# ESP32-MoonLolita-PCB.net
KiCad netlist of a schematic drawn in EasyEDA
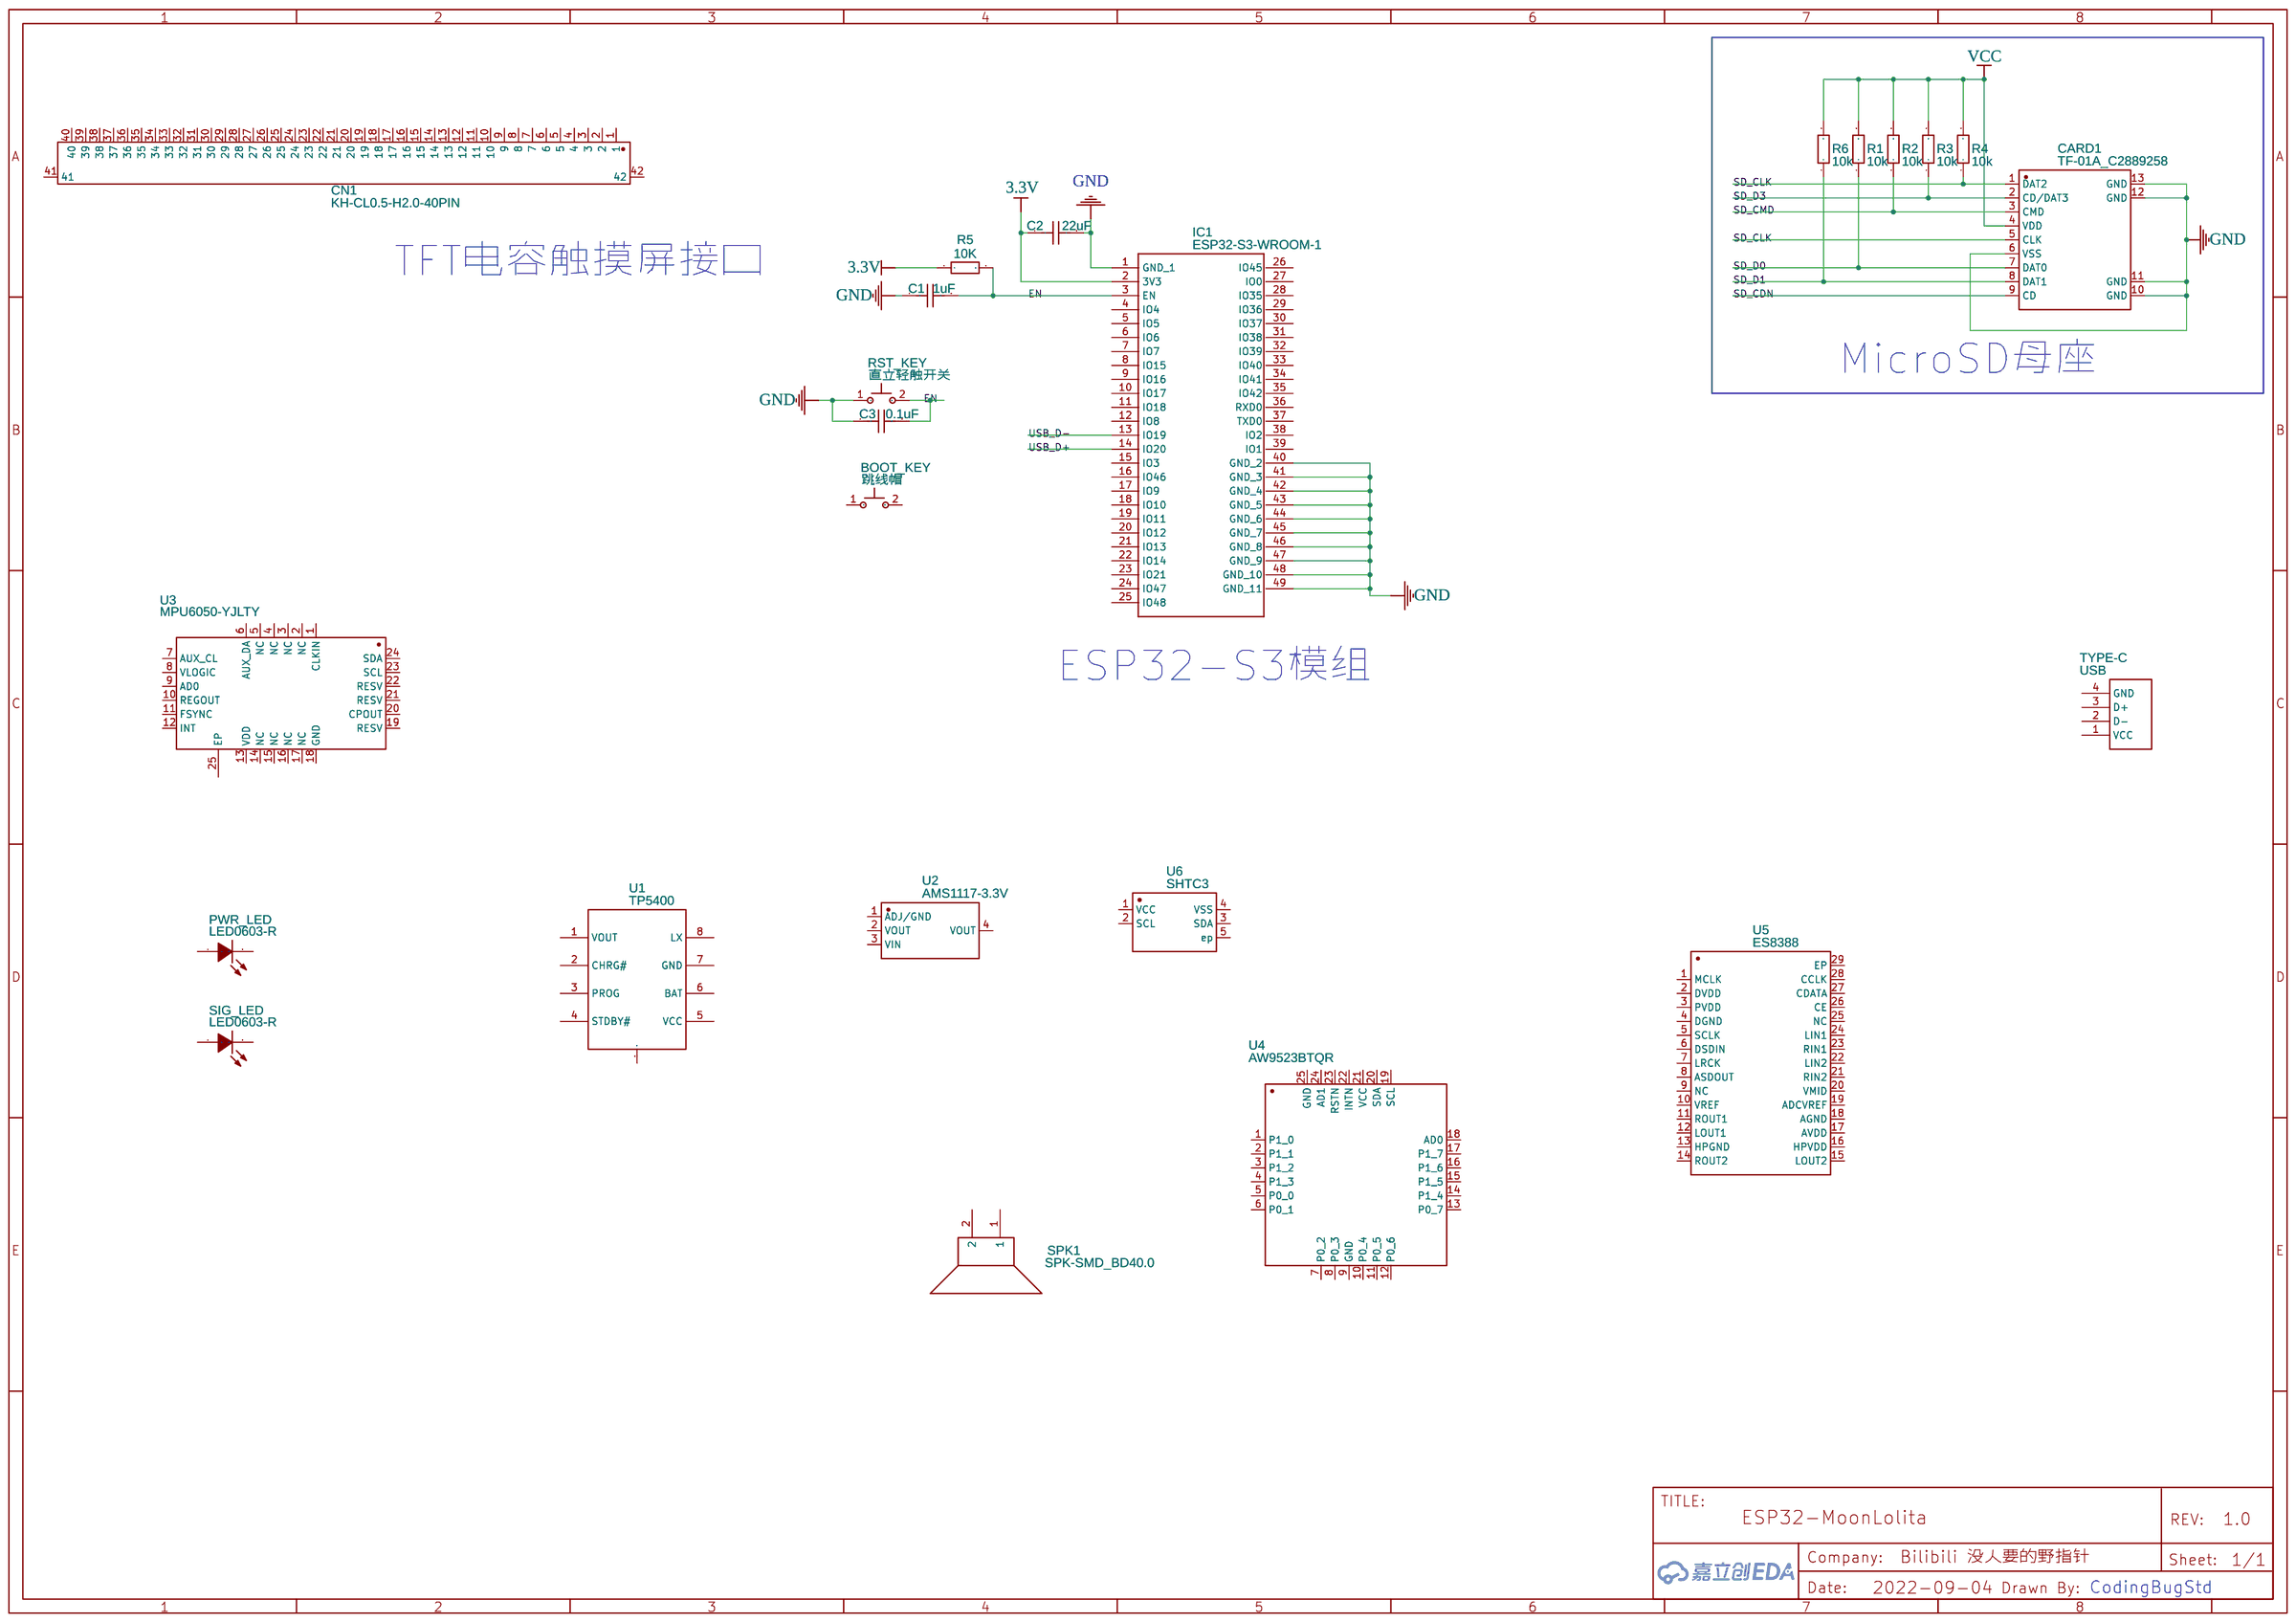
[diagram p0: schematic sheet]

(export (version "E")
  (design (tool "Eeschema 10.0.6"))
  (components
    (comp (ref "BOOT_KEY")
      (value "跳线帽")
      (fields
        (field (name "BOM_Manufacturer Part") "KSS341GLFS")
        (field (name "BOM_Supplier Part") "C221798")
      )
      (libsource (lib "") (part "KSS341GLFS_1"))
    )
    (comp (ref "C1")
      (value "1uF")
      (fields (field (name "BOM_Supplier Part") "C185991"))
      (libsource (lib "") (part "FGSM(161) 630VDC 224J 101F"))
    )
    (comp (ref "C2")
      (value "22uF")
      (fields (field (name "BOM_Supplier Part") "C185991"))
      (libsource (lib "") (part "FGSM(161) 630VDC 224J 101F"))
    )
    (comp (ref "C3")
      (value "0.1uF")
      (fields (field (name "BOM_Supplier Part") "C185991"))
      (libsource (lib "") (part "FGSM(161) 630VDC 224J 101F"))
    )
    (comp (ref "CARD1")
      (value "TF-01A_C2889258")
      (fields (field (name "BOM_Manufacturer Part") "TF-01A") (field (name "BOM_Supplier Part") "C2889258"))
      (libsource (lib "") (part "TF-01A_C2889258"))
    )
    (comp (ref "CN1")
      (value "KH-CL0.5-H2.0-40PIN")
      (fields (field (name "BOM_Supplier Part") "C2797203"))
      (libsource (lib "") (part "KH-CL0.5-H2.0-40PIN"))
    )
    (comp (ref "IC1") (value "ESP32-S3-WROOM-1") (libsource (lib "") (part "ESP32-S3-WROOM-1")))
    (comp (ref "PWR_LED")
      (value "LED0603-R")
      (fields (field (name "BOM_Supplier Part") "C9900005326"))
      (libsource (lib "") (part "LED0603-R_1"))
    )
    (comp (ref "R1")
      (value "10k")
      (fields (field (name "BOM_Manufacturer Part") "电阻0805"))
      (libsource (lib "") (part "电阻0603"))
    )
    (comp (ref "R2")
      (value "10k")
      (fields (field (name "BOM_Manufacturer Part") "电阻0805"))
      (libsource (lib "") (part "电阻0603"))
    )
    (comp (ref "R3")
      (value "10k")
      (fields (field (name "BOM_Manufacturer Part") "电阻0805"))
      (libsource (lib "") (part "电阻0603"))
    )
    (comp (ref "R4")
      (value "10k")
      (fields (field (name "BOM_Manufacturer Part") "电阻0805"))
      (libsource (lib "") (part "电阻0603"))
    )
    (comp (ref "R5")
      (value "10K")
      (fields
        (field (name "BOM_Manufacturer Part") "1206W4F1212T5E")
        (field (name "BOM_Supplier Part") "C247391")
      )
      (libsource (lib "") (part "1206W4F1212T5E"))
    )
    (comp (ref "R6")
      (value "10k")
      (fields (field (name "BOM_Manufacturer Part") "电阻0805"))
      (libsource (lib "") (part "电阻0603"))
    )
    (comp (ref "RST_KEY")
      (value "直立轻触开关")
      (fields
        (field (name "BOM_Manufacturer Part") "KSS341GLFS")
        (field (name "BOM_Supplier Part") "C221798")
      )
      (libsource (lib "") (part "KSS341GLFS"))
    )
    (comp (ref "SIG_LED")
      (value "LED0603-R")
      (fields (field (name "BOM_Supplier Part") "C9900005326"))
      (libsource (lib "") (part "LED0603-R"))
    )
    (comp (ref "SPK1") (value "SPK-SMD_BD40.0") (libsource (lib "") (part "SPK-SMD_BD40.0")))
    (comp (ref "TYPE-C")
      (value "USB")
      (fields
        (field (name "BOM_Manufacturer Part") "U-USBAR04P-F000")
        (field (name "BOM_Supplier Part") "C386740")
      )
      (libsource (lib "") (part "USB"))
    )
    (comp (ref "U1")
      (value "TP5400")
      (fields (field (name "BOM_Supplier Part") "C24154"))
      (libsource (lib "") (part "TP5400"))
    )
    (comp (ref "U2")
      (value "AMS1117-3.3V")
      (fields (field (name "BOM_Supplier Part") "C2688239"))
      (libsource (lib "") (part "AMS1117-3.3V"))
    )
    (comp (ref "U3")
      (value "MPU6050-YJLTY")
      (fields (field (name "BOM_Supplier Part") "C2912107"))
      (libsource (lib "") (part "MPU6050-YJLTY"))
    )
    (comp (ref "U4")
      (value "AW9523BTQR")
      (fields (field (name "BOM_Supplier Part") "C148077"))
      (libsource (lib "") (part "AW9523BTQR"))
    )
    (comp (ref "U5")
      (value "ES8388")
      (fields (field (name "BOM_Supplier Part") "C365736"))
      (libsource (lib "") (part "ES8388"))
    )
    (comp (ref "U6")
      (value "SHTC3")
      (fields (field (name "BOM_Supplier Part") "C194656"))
      (libsource (lib "") (part "SHTC3"))
    )
  )
  (nets
    (net (code "1") (name "/EN") (class "Default")
      (node (ref "C1") (pin "2") (pinfunction "2_2") (pintype "unspecified"))
      (node (ref "C3") (pin "2") (pinfunction "2_2") (pintype "unspecified"))
      (node (ref "IC1") (pin "3") (pinfunction "EN_3") (pintype "bidirectional"))
      (node (ref "R5") (pin "2") (pinfunction "2_2") (pintype "unspecified"))
      (node (ref "RST_KEY") (pin "2") (pinfunction "2_2") (pintype "unspecified"))
    )
    (net (code "2") (name "/SD_CDN") (class "Default")
      (node (ref "CARD1") (pin "9") (pinfunction "CD_9") (pintype "unspecified"))
    )
    (net (code "3") (name "/SD_CLK") (class "Default")
      (node (ref "CARD1") (pin "1") (pinfunction "DAT2_1") (pintype "unspecified"))
      (node (ref "CARD1") (pin "5") (pinfunction "CLK_5") (pintype "unspecified"))
      (node (ref "R4") (pin "1") (pinfunction "1_1") (pintype "input"))
    )
    (net (code "4") (name "/SD_CMD") (class "Default")
      (node (ref "CARD1") (pin "3") (pinfunction "CMD_3") (pintype "unspecified"))
      (node (ref "R2") (pin "1") (pinfunction "1_1") (pintype "input"))
    )
    (net (code "5") (name "/SD_D0") (class "Default")
      (node (ref "CARD1") (pin "7") (pinfunction "DAT0_7") (pintype "unspecified"))
      (node (ref "R1") (pin "1") (pinfunction "1_1") (pintype "input"))
    )
    (net (code "6") (name "/SD_D1") (class "Default")
      (node (ref "CARD1") (pin "8") (pinfunction "DAT1_8") (pintype "unspecified"))
      (node (ref "R6") (pin "1") (pinfunction "1_1") (pintype "input"))
    )
    (net (code "7") (name "/SD_D3") (class "Default")
      (node (ref "CARD1") (pin "2") (pinfunction "CD/DAT3_2") (pintype "unspecified"))
      (node (ref "R3") (pin "1") (pinfunction "1_1") (pintype "input"))
    )
    (net (code "8") (name "/USB_D+") (class "Default")
      (node (ref "IC1") (pin "14") (pinfunction "IO20_14") (pintype "bidirectional"))
    )
    (net (code "9") (name "/USB_D-") (class "Default")
      (node (ref "IC1") (pin "13") (pinfunction "IO19_13") (pintype "bidirectional"))
    )
    (net (code "10") (name "3.3V") (class "Default")
      (node (ref "C2") (pin "1") (pinfunction "1_1") (pintype "unspecified"))
      (node (ref "IC1") (pin "2") (pinfunction "3V3_2") (pintype "bidirectional"))
      (node (ref "R5") (pin "1") (pinfunction "1_1") (pintype "unspecified"))
    )
    (net (code "11") (name "GND") (class "Default")
      (node (ref "C1") (pin "1") (pinfunction "1_1") (pintype "unspecified"))
      (node (ref "C2") (pin "2") (pinfunction "2_2") (pintype "unspecified"))
      (node (ref "C3") (pin "1") (pinfunction "1_1") (pintype "unspecified"))
      (node (ref "CARD1") (pin "10") (pinfunction "GND_10") (pintype "unspecified"))
      (node (ref "CARD1") (pin "11") (pinfunction "GND_11") (pintype "unspecified"))
      (node (ref "CARD1") (pin "12") (pinfunction "GND_12") (pintype "unspecified"))
      (node (ref "CARD1") (pin "13") (pinfunction "GND_13") (pintype "unspecified"))
      (node (ref "CARD1") (pin "6") (pinfunction "VSS_6") (pintype "unspecified"))
      (node (ref "IC1") (pin "1") (pinfunction "GND_1_1") (pintype "bidirectional"))
      (node (ref "IC1") (pin "40") (pinfunction "GND_2_40") (pintype "bidirectional"))
      (node (ref "IC1") (pin "41") (pinfunction "GND_3_41") (pintype "bidirectional"))
      (node (ref "IC1") (pin "42") (pinfunction "GND_4_42") (pintype "bidirectional"))
      (node (ref "IC1") (pin "43") (pinfunction "GND_5_43") (pintype "bidirectional"))
      (node (ref "IC1") (pin "44") (pinfunction "GND_6_44") (pintype "bidirectional"))
      (node (ref "IC1") (pin "45") (pinfunction "GND_7_45") (pintype "bidirectional"))
      (node (ref "IC1") (pin "46") (pinfunction "GND_8_46") (pintype "bidirectional"))
      (node (ref "IC1") (pin "47") (pinfunction "GND_9_47") (pintype "bidirectional"))
      (node (ref "IC1") (pin "48") (pinfunction "GND_10_48") (pintype "bidirectional"))
      (node (ref "IC1") (pin "49") (pinfunction "GND_11_49") (pintype "bidirectional"))
      (node (ref "RST_KEY") (pin "1") (pinfunction "1_1") (pintype "unspecified"))
    )
    (net (code "12") (name "VCC") (class "Default")
      (node (ref "CARD1") (pin "4") (pinfunction "VDD_4") (pintype "unspecified"))
      (node (ref "R1") (pin "2") (pinfunction "2_2") (pintype "input"))
      (node (ref "R2") (pin "2") (pinfunction "2_2") (pintype "input"))
      (node (ref "R3") (pin "2") (pinfunction "2_2") (pintype "input"))
      (node (ref "R4") (pin "2") (pinfunction "2_2") (pintype "input"))
      (node (ref "R6") (pin "2") (pinfunction "2_2") (pintype "input"))
    )
    (net (code "13") (name "unconnected-(BOOT_KEY-Pad1)") (class "Default")
      (node (ref "BOOT_KEY") (pin "1") (pinfunction "1_1") (pintype "unspecified"))
    )
    (net (code "14") (name "unconnected-(BOOT_KEY-Pad2)") (class "Default")
      (node (ref "BOOT_KEY") (pin "2") (pinfunction "2_2") (pintype "unspecified"))
    )
    (net (code "15") (name "unconnected-(CN1-Pad1)") (class "Default")
      (node (ref "CN1") (pin "1") (pinfunction "1_1") (pintype "unspecified"))
    )
    (net (code "16") (name "unconnected-(CN1-Pad2)") (class "Default")
      (node (ref "CN1") (pin "2") (pinfunction "2_2") (pintype "unspecified"))
    )
    (net (code "17") (name "unconnected-(CN1-Pad3)") (class "Default")
      (node (ref "CN1") (pin "3") (pinfunction "3_3") (pintype "unspecified"))
    )
    (net (code "18") (name "unconnected-(CN1-Pad4)") (class "Default")
      (node (ref "CN1") (pin "4") (pinfunction "4_4") (pintype "unspecified"))
    )
    (net (code "19") (name "unconnected-(CN1-Pad5)") (class "Default")
      (node (ref "CN1") (pin "5") (pinfunction "5_5") (pintype "unspecified"))
    )
    (net (code "20") (name "unconnected-(CN1-Pad6)") (class "Default")
      (node (ref "CN1") (pin "6") (pinfunction "6_6") (pintype "unspecified"))
    )
    (net (code "21") (name "unconnected-(CN1-Pad7)") (class "Default")
      (node (ref "CN1") (pin "7") (pinfunction "7_7") (pintype "unspecified"))
    )
    (net (code "22") (name "unconnected-(CN1-Pad8)") (class "Default")
      (node (ref "CN1") (pin "8") (pinfunction "8_8") (pintype "unspecified"))
    )
    (net (code "23") (name "unconnected-(CN1-Pad9)") (class "Default")
      (node (ref "CN1") (pin "9") (pinfunction "9_9") (pintype "unspecified"))
    )
    (net (code "24") (name "unconnected-(CN1-Pad10)") (class "Default")
      (node (ref "CN1") (pin "10") (pinfunction "10_10") (pintype "unspecified"))
    )
    (net (code "25") (name "unconnected-(CN1-Pad11)") (class "Default")
      (node (ref "CN1") (pin "11") (pinfunction "11_11") (pintype "unspecified"))
    )
    (net (code "26") (name "unconnected-(CN1-Pad12)") (class "Default")
      (node (ref "CN1") (pin "12") (pinfunction "12_12") (pintype "unspecified"))
    )
    (net (code "27") (name "unconnected-(CN1-Pad13)") (class "Default")
      (node (ref "CN1") (pin "13") (pinfunction "13_13") (pintype "unspecified"))
    )
    (net (code "28") (name "unconnected-(CN1-Pad14)") (class "Default")
      (node (ref "CN1") (pin "14") (pinfunction "14_14") (pintype "unspecified"))
    )
    (net (code "29") (name "unconnected-(CN1-Pad15)") (class "Default")
      (node (ref "CN1") (pin "15") (pinfunction "15_15") (pintype "unspecified"))
    )
    (net (code "30") (name "unconnected-(CN1-Pad16)") (class "Default")
      (node (ref "CN1") (pin "16") (pinfunction "16_16") (pintype "unspecified"))
    )
    (net (code "31") (name "unconnected-(CN1-Pad17)") (class "Default")
      (node (ref "CN1") (pin "17") (pinfunction "17_17") (pintype "unspecified"))
    )
    (net (code "32") (name "unconnected-(CN1-Pad18)") (class "Default")
      (node (ref "CN1") (pin "18") (pinfunction "18_18") (pintype "unspecified"))
    )
    (net (code "33") (name "unconnected-(CN1-Pad19)") (class "Default")
      (node (ref "CN1") (pin "19") (pinfunction "19_19") (pintype "unspecified"))
    )
    (net (code "34") (name "unconnected-(CN1-Pad20)") (class "Default")
      (node (ref "CN1") (pin "20") (pinfunction "20_20") (pintype "unspecified"))
    )
    (net (code "35") (name "unconnected-(CN1-Pad21)") (class "Default")
      (node (ref "CN1") (pin "21") (pinfunction "21_21") (pintype "unspecified"))
    )
    (net (code "36") (name "unconnected-(CN1-Pad22)") (class "Default")
      (node (ref "CN1") (pin "22") (pinfunction "22_22") (pintype "unspecified"))
    )
    (net (code "37") (name "unconnected-(CN1-Pad23)") (class "Default")
      (node (ref "CN1") (pin "23") (pinfunction "23_23") (pintype "unspecified"))
    )
    (net (code "38") (name "unconnected-(CN1-Pad24)") (class "Default")
      (node (ref "CN1") (pin "24") (pinfunction "24_24") (pintype "unspecified"))
    )
    (net (code "39") (name "unconnected-(CN1-Pad25)") (class "Default")
      (node (ref "CN1") (pin "25") (pinfunction "25_25") (pintype "unspecified"))
    )
    (net (code "40") (name "unconnected-(CN1-Pad26)") (class "Default")
      (node (ref "CN1") (pin "26") (pinfunction "26_26") (pintype "unspecified"))
    )
    (net (code "41") (name "unconnected-(CN1-Pad27)") (class "Default")
      (node (ref "CN1") (pin "27") (pinfunction "27_27") (pintype "unspecified"))
    )
    (net (code "42") (name "unconnected-(CN1-Pad28)") (class "Default")
      (node (ref "CN1") (pin "28") (pinfunction "28_28") (pintype "unspecified"))
    )
    (net (code "43") (name "unconnected-(CN1-Pad29)") (class "Default")
      (node (ref "CN1") (pin "29") (pinfunction "29_29") (pintype "unspecified"))
    )
    (net (code "44") (name "unconnected-(CN1-Pad30)") (class "Default")
      (node (ref "CN1") (pin "30") (pinfunction "30_30") (pintype "unspecified"))
    )
    (net (code "45") (name "unconnected-(CN1-Pad31)") (class "Default")
      (node (ref "CN1") (pin "31") (pinfunction "31_31") (pintype "unspecified"))
    )
    (net (code "46") (name "unconnected-(CN1-Pad32)") (class "Default")
      (node (ref "CN1") (pin "32") (pinfunction "32_32") (pintype "unspecified"))
    )
    (net (code "47") (name "unconnected-(CN1-Pad33)") (class "Default")
      (node (ref "CN1") (pin "33") (pinfunction "33_33") (pintype "unspecified"))
    )
    (net (code "48") (name "unconnected-(CN1-Pad34)") (class "Default")
      (node (ref "CN1") (pin "34") (pinfunction "34_34") (pintype "unspecified"))
    )
    (net (code "49") (name "unconnected-(CN1-Pad35)") (class "Default")
      (node (ref "CN1") (pin "35") (pinfunction "35_35") (pintype "unspecified"))
    )
    (net (code "50") (name "unconnected-(CN1-Pad36)") (class "Default")
      (node (ref "CN1") (pin "36") (pinfunction "36_36") (pintype "unspecified"))
    )
    (net (code "51") (name "unconnected-(CN1-Pad37)") (class "Default")
      (node (ref "CN1") (pin "37") (pinfunction "37_37") (pintype "unspecified"))
    )
    (net (code "52") (name "unconnected-(CN1-Pad38)") (class "Default")
      (node (ref "CN1") (pin "38") (pinfunction "38_38") (pintype "unspecified"))
    )
    (net (code "53") (name "unconnected-(CN1-Pad39)") (class "Default")
      (node (ref "CN1") (pin "39") (pinfunction "39_39") (pintype "unspecified"))
    )
    (net (code "54") (name "unconnected-(CN1-Pad40)") (class "Default")
      (node (ref "CN1") (pin "40") (pinfunction "40_40") (pintype "unspecified"))
    )
    (net (code "55") (name "unconnected-(CN1-Pad41)") (class "Default")
      (node (ref "CN1") (pin "41") (pinfunction "41_41") (pintype "unspecified"))
    )
    (net (code "56") (name "unconnected-(CN1-Pad42)") (class "Default")
      (node (ref "CN1") (pin "42") (pinfunction "42_42") (pintype "unspecified"))
    )
    (net (code "57") (name "unconnected-(IC1-IO0-Pad27)") (class "Default")
      (node (ref "IC1") (pin "27") (pinfunction "IO0_27") (pintype "bidirectional"))
    )
    (net (code "58") (name "unconnected-(IC1-IO1-Pad39)") (class "Default")
      (node (ref "IC1") (pin "39") (pinfunction "IO1_39") (pintype "bidirectional"))
    )
    (net (code "59") (name "unconnected-(IC1-IO2-Pad38)") (class "Default")
      (node (ref "IC1") (pin "38") (pinfunction "IO2_38") (pintype "bidirectional"))
    )
    (net (code "60") (name "unconnected-(IC1-IO3-Pad15)") (class "Default")
      (node (ref "IC1") (pin "15") (pinfunction "IO3_15") (pintype "bidirectional"))
    )
    (net (code "61") (name "unconnected-(IC1-IO4-Pad4)") (class "Default")
      (node (ref "IC1") (pin "4") (pinfunction "IO4_4") (pintype "bidirectional"))
    )
    (net (code "62") (name "unconnected-(IC1-IO5-Pad5)") (class "Default")
      (node (ref "IC1") (pin "5") (pinfunction "IO5_5") (pintype "bidirectional"))
    )
    (net (code "63") (name "unconnected-(IC1-IO6-Pad6)") (class "Default")
      (node (ref "IC1") (pin "6") (pinfunction "IO6_6") (pintype "bidirectional"))
    )
    (net (code "64") (name "unconnected-(IC1-IO7-Pad7)") (class "Default")
      (node (ref "IC1") (pin "7") (pinfunction "IO7_7") (pintype "bidirectional"))
    )
    (net (code "65") (name "unconnected-(IC1-IO8-Pad12)") (class "Default")
      (node (ref "IC1") (pin "12") (pinfunction "IO8_12") (pintype "bidirectional"))
    )
    (net (code "66") (name "unconnected-(IC1-IO9-Pad17)") (class "Default")
      (node (ref "IC1") (pin "17") (pinfunction "IO9_17") (pintype "bidirectional"))
    )
    (net (code "67") (name "unconnected-(IC1-IO10-Pad18)") (class "Default")
      (node (ref "IC1") (pin "18") (pinfunction "IO10_18") (pintype "bidirectional"))
    )
    (net (code "68") (name "unconnected-(IC1-IO11-Pad19)") (class "Default")
      (node (ref "IC1") (pin "19") (pinfunction "IO11_19") (pintype "bidirectional"))
    )
    (net (code "69") (name "unconnected-(IC1-IO12-Pad20)") (class "Default")
      (node (ref "IC1") (pin "20") (pinfunction "IO12_20") (pintype "bidirectional"))
    )
    (net (code "70") (name "unconnected-(IC1-IO13-Pad21)") (class "Default")
      (node (ref "IC1") (pin "21") (pinfunction "IO13_21") (pintype "bidirectional"))
    )
    (net (code "71") (name "unconnected-(IC1-IO14-Pad22)") (class "Default")
      (node (ref "IC1") (pin "22") (pinfunction "IO14_22") (pintype "bidirectional"))
    )
    (net (code "72") (name "unconnected-(IC1-IO15-Pad8)") (class "Default")
      (node (ref "IC1") (pin "8") (pinfunction "IO15_8") (pintype "bidirectional"))
    )
    (net (code "73") (name "unconnected-(IC1-IO16-Pad9)") (class "Default")
      (node (ref "IC1") (pin "9") (pinfunction "IO16_9") (pintype "bidirectional"))
    )
    (net (code "74") (name "unconnected-(IC1-IO17-Pad10)") (class "Default")
      (node (ref "IC1") (pin "10") (pinfunction "IO17_10") (pintype "bidirectional"))
    )
    (net (code "75") (name "unconnected-(IC1-IO18-Pad11)") (class "Default")
      (node (ref "IC1") (pin "11") (pinfunction "IO18_11") (pintype "bidirectional"))
    )
    (net (code "76") (name "unconnected-(IC1-IO21-Pad23)") (class "Default")
      (node (ref "IC1") (pin "23") (pinfunction "IO21_23") (pintype "bidirectional"))
    )
    (net (code "77") (name "unconnected-(IC1-IO35-Pad28)") (class "Default")
      (node (ref "IC1") (pin "28") (pinfunction "IO35_28") (pintype "bidirectional"))
    )
    (net (code "78") (name "unconnected-(IC1-IO36-Pad29)") (class "Default")
      (node (ref "IC1") (pin "29") (pinfunction "IO36_29") (pintype "bidirectional"))
    )
    (net (code "79") (name "unconnected-(IC1-IO37-Pad30)") (class "Default")
      (node (ref "IC1") (pin "30") (pinfunction "IO37_30") (pintype "bidirectional"))
    )
    (net (code "80") (name "unconnected-(IC1-IO38-Pad31)") (class "Default")
      (node (ref "IC1") (pin "31") (pinfunction "IO38_31") (pintype "bidirectional"))
    )
    (net (code "81") (name "unconnected-(IC1-IO39-Pad32)") (class "Default")
      (node (ref "IC1") (pin "32") (pinfunction "IO39_32") (pintype "bidirectional"))
    )
    (net (code "82") (name "unconnected-(IC1-IO40-Pad33)") (class "Default")
      (node (ref "IC1") (pin "33") (pinfunction "IO40_33") (pintype "bidirectional"))
    )
    (net (code "83") (name "unconnected-(IC1-IO41-Pad34)") (class "Default")
      (node (ref "IC1") (pin "34") (pinfunction "IO41_34") (pintype "bidirectional"))
    )
    (net (code "84") (name "unconnected-(IC1-IO42-Pad35)") (class "Default")
      (node (ref "IC1") (pin "35") (pinfunction "IO42_35") (pintype "bidirectional"))
    )
    (net (code "85") (name "unconnected-(IC1-IO45-Pad26)") (class "Default")
      (node (ref "IC1") (pin "26") (pinfunction "IO45_26") (pintype "bidirectional"))
    )
    (net (code "86") (name "unconnected-(IC1-IO46-Pad16)") (class "Default")
      (node (ref "IC1") (pin "16") (pinfunction "IO46_16") (pintype "bidirectional"))
    )
    (net (code "87") (name "unconnected-(IC1-IO47-Pad24)") (class "Default")
      (node (ref "IC1") (pin "24") (pinfunction "IO47_24") (pintype "bidirectional"))
    )
    (net (code "88") (name "unconnected-(IC1-IO48-Pad25)") (class "Default")
      (node (ref "IC1") (pin "25") (pinfunction "IO48_25") (pintype "bidirectional"))
    )
    (net (code "89") (name "unconnected-(IC1-RXD0-Pad36)") (class "Default")
      (node (ref "IC1") (pin "36") (pinfunction "RXD0_36") (pintype "bidirectional"))
    )
    (net (code "90") (name "unconnected-(IC1-TXD0-Pad37)") (class "Default")
      (node (ref "IC1") (pin "37") (pinfunction "TXD0_37") (pintype "bidirectional"))
    )
    (net (code "91") (name "unconnected-(PWR_LED-A-Pad1)") (class "Default")
      (node (ref "PWR_LED") (pin "1") (pinfunction "A_1") (pintype "unspecified"))
    )
    (net (code "92") (name "unconnected-(PWR_LED-K-Pad2)") (class "Default")
      (node (ref "PWR_LED") (pin "2") (pinfunction "K_2") (pintype "unspecified"))
    )
    (net (code "93") (name "unconnected-(SIG_LED-A-Pad1)") (class "Default")
      (node (ref "SIG_LED") (pin "1") (pinfunction "A_1") (pintype "unspecified"))
    )
    (net (code "94") (name "unconnected-(SIG_LED-K-Pad2)") (class "Default")
      (node (ref "SIG_LED") (pin "2") (pinfunction "K_2") (pintype "unspecified"))
    )
    (net (code "95") (name "unconnected-(SPK1-Pad1)") (class "Default")
      (node (ref "SPK1") (pin "1") (pinfunction "1_1") (pintype "unspecified"))
    )
    (net (code "96") (name "unconnected-(SPK1-Pad2)") (class "Default")
      (node (ref "SPK1") (pin "2") (pinfunction "2_2") (pintype "unspecified"))
    )
    (net (code "97") (name "unconnected-(TYPE-C-D+-Pad3)") (class "Default")
      (node (ref "TYPE-C") (pin "3") (pinfunction "D+_3") (pintype "unspecified"))
    )
    (net (code "98") (name "unconnected-(TYPE-C-D--Pad2)") (class "Default")
      (node (ref "TYPE-C") (pin "2") (pinfunction "D-_2") (pintype "unspecified"))
    )
    (net (code "99") (name "unconnected-(TYPE-C-GND-Pad4)") (class "Default")
      (node (ref "TYPE-C") (pin "4") (pinfunction "GND_4") (pintype "unspecified"))
    )
    (net (code "100") (name "unconnected-(TYPE-C-VCC-Pad1)") (class "Default")
      (node (ref "TYPE-C") (pin "1") (pinfunction "VCC_1") (pintype "unspecified"))
    )
    (net (code "101") (name "unconnected-(U1-BAT-Pad6)") (class "Default")
      (node (ref "U1") (pin "6") (pinfunction "BAT_6") (pintype "unspecified"))
    )
    (net (code "102") (name "unconnected-(U1-CHRG#-Pad2)") (class "Default")
      (node (ref "U1") (pin "2") (pinfunction "CHRG#_2") (pintype "unspecified"))
    )
    (net (code "103") (name "unconnected-(U1-GND-Pad7)") (class "Default")
      (node (ref "U1") (pin "7") (pinfunction "GND_7") (pintype "unspecified"))
    )
    (net (code "104") (name "unconnected-(U1-LX-Pad8)") (class "Default")
      (node (ref "U1") (pin "8") (pinfunction "LX_8") (pintype "unspecified"))
    )
    (net (code "105") (name "unconnected-(U1-PROG-Pad3)") (class "Default")
      (node (ref "U1") (pin "3") (pinfunction "PROG_3") (pintype "unspecified"))
    )
    (net (code "106") (name "unconnected-(U1-Pad9)") (class "Default")
      (node (ref "U1") (pin "9") (pinfunction "9_9") (pintype "unspecified"))
    )
    (net (code "107") (name "unconnected-(U1-STDBY#-Pad4)") (class "Default")
      (node (ref "U1") (pin "4") (pinfunction "STDBY#_4") (pintype "unspecified"))
    )
    (net (code "108") (name "unconnected-(U1-VCC-Pad5)") (class "Default")
      (node (ref "U1") (pin "5") (pinfunction "VCC_5") (pintype "unspecified"))
    )
    (net (code "109") (name "unconnected-(U1-VOUT-Pad1)") (class "Default")
      (node (ref "U1") (pin "1") (pinfunction "VOUT_1") (pintype "unspecified"))
    )
    (net (code "110") (name "unconnected-(U2-ADJ{slash}GND-Pad1)") (class "Default")
      (node (ref "U2") (pin "1") (pinfunction "ADJ/GND_1") (pintype "unspecified"))
    )
    (net (code "111") (name "unconnected-(U2-VIN-Pad3)") (class "Default")
      (node (ref "U2") (pin "3") (pinfunction "VIN_3") (pintype "unspecified"))
    )
    (net (code "112") (name "unconnected-(U2-VOUT-Pad2)") (class "Default")
      (node (ref "U2") (pin "2") (pinfunction "VOUT_2") (pintype "unspecified"))
    )
    (net (code "113") (name "unconnected-(U2-VOUT-Pad4)") (class "Default")
      (node (ref "U2") (pin "4") (pinfunction "VOUT_4") (pintype "unspecified"))
    )
    (net (code "114") (name "unconnected-(U3-AD0-Pad9)") (class "Default")
      (node (ref "U3") (pin "9") (pinfunction "AD0_9") (pintype "unspecified"))
    )
    (net (code "115") (name "unconnected-(U3-AUX_CL-Pad7)") (class "Default")
      (node (ref "U3") (pin "7") (pinfunction "AUX_CL_7") (pintype "unspecified"))
    )
    (net (code "116") (name "unconnected-(U3-AUX_DA-Pad6)") (class "Default")
      (node (ref "U3") (pin "6") (pinfunction "AUX_DA_6") (pintype "unspecified"))
    )
    (net (code "117") (name "unconnected-(U3-CLKIN-Pad1)") (class "Default")
      (node (ref "U3") (pin "1") (pinfunction "CLKIN_1") (pintype "unspecified"))
    )
    (net (code "118") (name "unconnected-(U3-CPOUT-Pad20)") (class "Default")
      (node (ref "U3") (pin "20") (pinfunction "CPOUT_20") (pintype "unspecified"))
    )
    (net (code "119") (name "unconnected-(U3-EP-Pad25)") (class "Default")
      (node (ref "U3") (pin "25") (pinfunction "EP_25") (pintype "unspecified"))
    )
    (net (code "120") (name "unconnected-(U3-FSYNC-Pad11)") (class "Default")
      (node (ref "U3") (pin "11") (pinfunction "FSYNC_11") (pintype "unspecified"))
    )
    (net (code "121") (name "unconnected-(U3-GND-Pad18)") (class "Default")
      (node (ref "U3") (pin "18") (pinfunction "GND_18") (pintype "unspecified"))
    )
    (net (code "122") (name "unconnected-(U3-INT-Pad12)") (class "Default")
      (node (ref "U3") (pin "12") (pinfunction "INT_12") (pintype "unspecified"))
    )
    (net (code "123") (name "unconnected-(U3-NC-Pad2)") (class "Default")
      (node (ref "U3") (pin "2") (pinfunction "NC_2") (pintype "unspecified"))
    )
    (net (code "124") (name "unconnected-(U3-NC-Pad3)") (class "Default")
      (node (ref "U3") (pin "3") (pinfunction "NC_3") (pintype "unspecified"))
    )
    (net (code "125") (name "unconnected-(U3-NC-Pad4)") (class "Default")
      (node (ref "U3") (pin "4") (pinfunction "NC_4") (pintype "unspecified"))
    )
    (net (code "126") (name "unconnected-(U3-NC-Pad5)") (class "Default")
      (node (ref "U3") (pin "5") (pinfunction "NC_5") (pintype "unspecified"))
    )
    (net (code "127") (name "unconnected-(U3-NC-Pad14)") (class "Default")
      (node (ref "U3") (pin "14") (pinfunction "NC_14") (pintype "unspecified"))
    )
    (net (code "128") (name "unconnected-(U3-NC-Pad15)") (class "Default")
      (node (ref "U3") (pin "15") (pinfunction "NC_15") (pintype "unspecified"))
    )
    (net (code "129") (name "unconnected-(U3-NC-Pad16)") (class "Default")
      (node (ref "U3") (pin "16") (pinfunction "NC_16") (pintype "unspecified"))
    )
    (net (code "130") (name "unconnected-(U3-NC-Pad17)") (class "Default")
      (node (ref "U3") (pin "17") (pinfunction "NC_17") (pintype "unspecified"))
    )
    (net (code "131") (name "unconnected-(U3-REGOUT-Pad10)") (class "Default")
      (node (ref "U3") (pin "10") (pinfunction "REGOUT_10") (pintype "unspecified"))
    )
    (net (code "132") (name "unconnected-(U3-RESV-Pad19)") (class "Default")
      (node (ref "U3") (pin "19") (pinfunction "RESV_19") (pintype "unspecified"))
    )
    (net (code "133") (name "unconnected-(U3-RESV-Pad21)") (class "Default")
      (node (ref "U3") (pin "21") (pinfunction "RESV_21") (pintype "unspecified"))
    )
    (net (code "134") (name "unconnected-(U3-RESV-Pad22)") (class "Default")
      (node (ref "U3") (pin "22") (pinfunction "RESV_22") (pintype "unspecified"))
    )
    (net (code "135") (name "unconnected-(U3-SCL-Pad23)") (class "Default")
      (node (ref "U3") (pin "23") (pinfunction "SCL_23") (pintype "unspecified"))
    )
    (net (code "136") (name "unconnected-(U3-SDA-Pad24)") (class "Default")
      (node (ref "U3") (pin "24") (pinfunction "SDA_24") (pintype "unspecified"))
    )
    (net (code "137") (name "unconnected-(U3-VDD-Pad13)") (class "Default")
      (node (ref "U3") (pin "13") (pinfunction "VDD_13") (pintype "unspecified"))
    )
    (net (code "138") (name "unconnected-(U3-VLOGIC-Pad8)") (class "Default")
      (node (ref "U3") (pin "8") (pinfunction "VLOGIC_8") (pintype "unspecified"))
    )
    (net (code "139") (name "unconnected-(U4-AD0-Pad18)") (class "Default")
      (node (ref "U4") (pin "18") (pinfunction "AD0_18") (pintype "unspecified"))
    )
    (net (code "140") (name "unconnected-(U4-AD1-Pad24)") (class "Default")
      (node (ref "U4") (pin "24") (pinfunction "AD1_24") (pintype "unspecified"))
    )
    (net (code "141") (name "unconnected-(U4-GND-Pad9)") (class "Default")
      (node (ref "U4") (pin "9") (pinfunction "GND_9") (pintype "unspecified"))
    )
    (net (code "142") (name "unconnected-(U4-GND-Pad25)") (class "Default")
      (node (ref "U4") (pin "25") (pinfunction "GND_25") (pintype "unspecified"))
    )
    (net (code "143") (name "unconnected-(U4-INTN-Pad22)") (class "Default")
      (node (ref "U4") (pin "22") (pinfunction "INTN_22") (pintype "unspecified"))
    )
    (net (code "144") (name "unconnected-(U4-P0_0-Pad5)") (class "Default")
      (node (ref "U4") (pin "5") (pinfunction "P0_0_5") (pintype "unspecified"))
    )
    (net (code "145") (name "unconnected-(U4-P0_1-Pad6)") (class "Default")
      (node (ref "U4") (pin "6") (pinfunction "P0_1_6") (pintype "unspecified"))
    )
    (net (code "146") (name "unconnected-(U4-P0_2-Pad7)") (class "Default")
      (node (ref "U4") (pin "7") (pinfunction "P0_2_7") (pintype "unspecified"))
    )
    (net (code "147") (name "unconnected-(U4-P0_3-Pad8)") (class "Default")
      (node (ref "U4") (pin "8") (pinfunction "P0_3_8") (pintype "unspecified"))
    )
    (net (code "148") (name "unconnected-(U4-P0_4-Pad10)") (class "Default")
      (node (ref "U4") (pin "10") (pinfunction "P0_4_10") (pintype "unspecified"))
    )
    (net (code "149") (name "unconnected-(U4-P0_5-Pad11)") (class "Default")
      (node (ref "U4") (pin "11") (pinfunction "P0_5_11") (pintype "unspecified"))
    )
    (net (code "150") (name "unconnected-(U4-P0_6-Pad12)") (class "Default")
      (node (ref "U4") (pin "12") (pinfunction "P0_6_12") (pintype "unspecified"))
    )
    (net (code "151") (name "unconnected-(U4-P0_7-Pad13)") (class "Default")
      (node (ref "U4") (pin "13") (pinfunction "P0_7_13") (pintype "unspecified"))
    )
    (net (code "152") (name "unconnected-(U4-P1_0-Pad1)") (class "Default")
      (node (ref "U4") (pin "1") (pinfunction "P1_0_1") (pintype "unspecified"))
    )
    (net (code "153") (name "unconnected-(U4-P1_1-Pad2)") (class "Default")
      (node (ref "U4") (pin "2") (pinfunction "P1_1_2") (pintype "unspecified"))
    )
    (net (code "154") (name "unconnected-(U4-P1_2-Pad3)") (class "Default")
      (node (ref "U4") (pin "3") (pinfunction "P1_2_3") (pintype "unspecified"))
    )
    (net (code "155") (name "unconnected-(U4-P1_3-Pad4)") (class "Default")
      (node (ref "U4") (pin "4") (pinfunction "P1_3_4") (pintype "unspecified"))
    )
    (net (code "156") (name "unconnected-(U4-P1_4-Pad14)") (class "Default")
      (node (ref "U4") (pin "14") (pinfunction "P1_4_14") (pintype "unspecified"))
    )
    (net (code "157") (name "unconnected-(U4-P1_5-Pad15)") (class "Default")
      (node (ref "U4") (pin "15") (pinfunction "P1_5_15") (pintype "unspecified"))
    )
    (net (code "158") (name "unconnected-(U4-P1_6-Pad16)") (class "Default")
      (node (ref "U4") (pin "16") (pinfunction "P1_6_16") (pintype "unspecified"))
    )
    (net (code "159") (name "unconnected-(U4-P1_7-Pad17)") (class "Default")
      (node (ref "U4") (pin "17") (pinfunction "P1_7_17") (pintype "unspecified"))
    )
    (net (code "160") (name "unconnected-(U4-RSTN-Pad23)") (class "Default")
      (node (ref "U4") (pin "23") (pinfunction "RSTN_23") (pintype "unspecified"))
    )
    (net (code "161") (name "unconnected-(U4-SCL-Pad19)") (class "Default")
      (node (ref "U4") (pin "19") (pinfunction "SCL_19") (pintype "unspecified"))
    )
    (net (code "162") (name "unconnected-(U4-SDA-Pad20)") (class "Default")
      (node (ref "U4") (pin "20") (pinfunction "SDA_20") (pintype "unspecified"))
    )
    (net (code "163") (name "unconnected-(U4-VCC-Pad21)") (class "Default")
      (node (ref "U4") (pin "21") (pinfunction "VCC_21") (pintype "unspecified"))
    )
    (net (code "164") (name "unconnected-(U5-ADCVREF-Pad19)") (class "Default")
      (node (ref "U5") (pin "19") (pinfunction "ADCVREF_19") (pintype "unspecified"))
    )
    (net (code "165") (name "unconnected-(U5-AGND-Pad18)") (class "Default")
      (node (ref "U5") (pin "18") (pinfunction "AGND_18") (pintype "unspecified"))
    )
    (net (code "166") (name "unconnected-(U5-ASDOUT-Pad8)") (class "Default")
      (node (ref "U5") (pin "8") (pinfunction "ASDOUT_8") (pintype "unspecified"))
    )
    (net (code "167") (name "unconnected-(U5-AVDD-Pad17)") (class "Default")
      (node (ref "U5") (pin "17") (pinfunction "AVDD_17") (pintype "unspecified"))
    )
    (net (code "168") (name "unconnected-(U5-CCLK-Pad28)") (class "Default")
      (node (ref "U5") (pin "28") (pinfunction "CCLK_28") (pintype "unspecified"))
    )
    (net (code "169") (name "unconnected-(U5-CDATA-Pad27)") (class "Default")
      (node (ref "U5") (pin "27") (pinfunction "CDATA_27") (pintype "unspecified"))
    )
    (net (code "170") (name "unconnected-(U5-CE-Pad26)") (class "Default")
      (node (ref "U5") (pin "26") (pinfunction "CE_26") (pintype "unspecified"))
    )
    (net (code "171") (name "unconnected-(U5-DGND-Pad4)") (class "Default")
      (node (ref "U5") (pin "4") (pinfunction "DGND_4") (pintype "unspecified"))
    )
    (net (code "172") (name "unconnected-(U5-DSDIN-Pad6)") (class "Default")
      (node (ref "U5") (pin "6") (pinfunction "DSDIN_6") (pintype "unspecified"))
    )
    (net (code "173") (name "unconnected-(U5-DVDD-Pad2)") (class "Default")
      (node (ref "U5") (pin "2") (pinfunction "DVDD_2") (pintype "unspecified"))
    )
    (net (code "174") (name "unconnected-(U5-EP-Pad29)") (class "Default")
      (node (ref "U5") (pin "29") (pinfunction "EP_29") (pintype "unspecified"))
    )
    (net (code "175") (name "unconnected-(U5-HPGND-Pad13)") (class "Default")
      (node (ref "U5") (pin "13") (pinfunction "HPGND_13") (pintype "unspecified"))
    )
    (net (code "176") (name "unconnected-(U5-HPVDD-Pad16)") (class "Default")
      (node (ref "U5") (pin "16") (pinfunction "HPVDD_16") (pintype "unspecified"))
    )
    (net (code "177") (name "unconnected-(U5-LIN1-Pad24)") (class "Default")
      (node (ref "U5") (pin "24") (pinfunction "LIN1_24") (pintype "unspecified"))
    )
    (net (code "178") (name "unconnected-(U5-LIN2-Pad22)") (class "Default")
      (node (ref "U5") (pin "22") (pinfunction "LIN2_22") (pintype "unspecified"))
    )
    (net (code "179") (name "unconnected-(U5-LOUT1-Pad12)") (class "Default")
      (node (ref "U5") (pin "12") (pinfunction "LOUT1_12") (pintype "unspecified"))
    )
    (net (code "180") (name "unconnected-(U5-LOUT2-Pad15)") (class "Default")
      (node (ref "U5") (pin "15") (pinfunction "LOUT2_15") (pintype "unspecified"))
    )
    (net (code "181") (name "unconnected-(U5-LRCK-Pad7)") (class "Default")
      (node (ref "U5") (pin "7") (pinfunction "LRCK_7") (pintype "unspecified"))
    )
    (net (code "182") (name "unconnected-(U5-MCLK-Pad1)") (class "Default")
      (node (ref "U5") (pin "1") (pinfunction "MCLK_1") (pintype "unspecified"))
    )
    (net (code "183") (name "unconnected-(U5-NC-Pad9)") (class "Default")
      (node (ref "U5") (pin "9") (pinfunction "NC_9") (pintype "unspecified"))
    )
    (net (code "184") (name "unconnected-(U5-NC-Pad25)") (class "Default")
      (node (ref "U5") (pin "25") (pinfunction "NC_25") (pintype "unspecified"))
    )
    (net (code "185") (name "unconnected-(U5-PVDD-Pad3)") (class "Default")
      (node (ref "U5") (pin "3") (pinfunction "PVDD_3") (pintype "unspecified"))
    )
    (net (code "186") (name "unconnected-(U5-RIN1-Pad23)") (class "Default")
      (node (ref "U5") (pin "23") (pinfunction "RIN1_23") (pintype "unspecified"))
    )
    (net (code "187") (name "unconnected-(U5-RIN2-Pad21)") (class "Default")
      (node (ref "U5") (pin "21") (pinfunction "RIN2_21") (pintype "unspecified"))
    )
    (net (code "188") (name "unconnected-(U5-ROUT1-Pad11)") (class "Default")
      (node (ref "U5") (pin "11") (pinfunction "ROUT1_11") (pintype "unspecified"))
    )
    (net (code "189") (name "unconnected-(U5-ROUT2-Pad14)") (class "Default")
      (node (ref "U5") (pin "14") (pinfunction "ROUT2_14") (pintype "unspecified"))
    )
    (net (code "190") (name "unconnected-(U5-SCLK-Pad5)") (class "Default")
      (node (ref "U5") (pin "5") (pinfunction "SCLK_5") (pintype "unspecified"))
    )
    (net (code "191") (name "unconnected-(U5-VMID-Pad20)") (class "Default")
      (node (ref "U5") (pin "20") (pinfunction "VMID_20") (pintype "unspecified"))
    )
    (net (code "192") (name "unconnected-(U5-VREF-Pad10)") (class "Default")
      (node (ref "U5") (pin "10") (pinfunction "VREF_10") (pintype "unspecified"))
    )
    (net (code "193") (name "unconnected-(U6-SCL-Pad2)") (class "Default")
      (node (ref "U6") (pin "2") (pinfunction "SCL_2") (pintype "unspecified"))
    )
    (net (code "194") (name "unconnected-(U6-SDA-Pad3)") (class "Default")
      (node (ref "U6") (pin "3") (pinfunction "SDA_3") (pintype "unspecified"))
    )
    (net (code "195") (name "unconnected-(U6-VCC-Pad1)") (class "Default")
      (node (ref "U6") (pin "1") (pinfunction "VCC_1") (pintype "unspecified"))
    )
    (net (code "196") (name "unconnected-(U6-VSS-Pad4)") (class "Default")
      (node (ref "U6") (pin "4") (pinfunction "VSS_4") (pintype "unspecified"))
    )
    (net (code "197") (name "unconnected-(U6-ep-Pad5)") (class "Default")
      (node (ref "U6") (pin "5") (pinfunction "ep_5") (pintype "unspecified"))
    )
  )
)
